# QCopterFC_MCU_Sch.net
KiCad netlist of a schematic drawn in Altium Designer
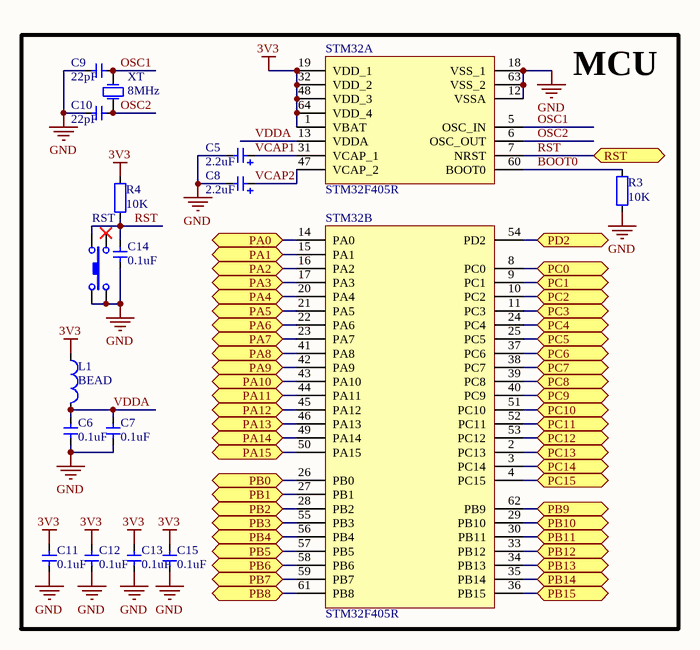
[diagram p0: QCopterFC_MCU_Sch.SchDoc]

(export (version "E")
  (design (tool "Eeschema 10.0.6"))
  (components
    (comp (ref "C5")
      (value "2.2uF")
      (footprint "PCB_Passive:CAP_TAN_P0805")
      (description "Capacitor")
      (fields (field (name "Comment") "Cap_Tan_0805"))
      (libsource (lib "SCH_Passive") (part "Cap_Tan_0805"))
    )
    (comp (ref "C6")
      (value "0.1uF")
      (footprint "PCB_Passive:CAP_0603")
      (description "Capacitor")
      (fields (field (name "Comment") "Cap_0603"))
      (libsource (lib "SCH_Passive") (part "Cap_0603"))
    )
    (comp (ref "C7")
      (value "0.1uF")
      (footprint "PCB_Passive:CAP_0603")
      (description "Capacitor")
      (fields (field (name "Comment") "Cap_0603"))
      (libsource (lib "SCH_Passive") (part "Cap_0603"))
    )
    (comp (ref "C8")
      (value "2.2uF")
      (footprint "PCB_Passive:CAP_TAN_P0805")
      (description "Capacitor")
      (fields (field (name "Comment") "Cap_Tan_0805"))
      (libsource (lib "SCH_Passive") (part "Cap_Tan_0805"))
    )
    (comp (ref "C9")
      (value "22pF")
      (footprint "PCB_Passive:CAP_0603")
      (description "Capacitor")
      (fields (field (name "Comment") "Cap_0603"))
      (libsource (lib "SCH_Passive") (part "Cap_0603"))
    )
    (comp (ref "C10")
      (value "22pF")
      (footprint "PCB_Passive:CAP_0603")
      (description "Capacitor")
      (fields (field (name "Comment") "Cap_0603"))
      (libsource (lib "SCH_Passive") (part "Cap_0603"))
    )
    (comp (ref "C11")
      (value "0.1uF")
      (footprint "PCB_Passive:CAP_0603")
      (description "Capacitor")
      (fields (field (name "Comment") "Cap_0603"))
      (libsource (lib "SCH_Passive") (part "Cap_0603"))
    )
    (comp (ref "C12")
      (value "0.1uF")
      (footprint "PCB_Passive:CAP_0603")
      (description "Capacitor")
      (fields (field (name "Comment") "Cap_0603"))
      (libsource (lib "SCH_Passive") (part "Cap_0603"))
    )
    (comp (ref "C13")
      (value "0.1uF")
      (footprint "PCB_Passive:CAP_0603")
      (description "Capacitor")
      (fields (field (name "Comment") "Cap_0603"))
      (libsource (lib "SCH_Passive") (part "Cap_0603"))
    )
    (comp (ref "C14")
      (value "0.1uF")
      (footprint "PCB_Passive:CAP_0603")
      (description "Capacitor")
      (fields (field (name "Comment") "Cap_0603"))
      (libsource (lib "SCH_Passive") (part "Cap_0603"))
    )
    (comp (ref "C15")
      (value "0.1uF")
      (footprint "PCB_Passive:CAP_0603")
      (description "Capacitor")
      (fields (field (name "Comment") "Cap_0603"))
      (libsource (lib "SCH_Passive") (part "Cap_0603"))
    )
    (comp (ref "L1")
      (value "BEAD")
      (footprint "PCB_Passive:IND_0603")
      (description "Inductor")
      (fields (field (name "Comment") "Ind_0603"))
      (libsource (lib "SCH_Passive") (part "Ind_0603"))
    )
    (comp (ref "R3")
      (value "10K")
      (footprint "PCB_Passive:RES_0603")
      (description "Resistor")
      (fields (field (name "Comment") "Res_0603"))
      (libsource (lib "SCH_Passive") (part "Res_0603"))
    )
    (comp (ref "R4")
      (value "10K")
      (footprint "PCB_Passive:RES_0603")
      (description "Resistor")
      (fields (field (name "Comment") "Res_0603"))
      (libsource (lib "SCH_Passive") (part "Res_0603"))
    )
    (comp (ref "RST")
      (value "BT_TACT_3.5*5_90")
      (footprint "PCB_Switch:BT_TACT_3.5*3.55_90")
      (description "Switch")
      (libsource (lib "SCH_Switch") (part "BT_TACT_3.5*5_90"))
    )
    (comp (ref "STM32")
      (value "STM32F405R")
      (footprint "PCB_IC:STM32_QFP64")
      (description "MCU")
      (libsource (lib "SCH_IC") (part "STM32F405R"))
    )
    (comp (ref "XT")
      (value "8MHz")
      (footprint "PCB_Oscillator:XTAL_5032")
      (description "Crystal Oscillator")
      (fields (field (name "Comment") "XTAL_5032_2P"))
      (libsource (lib "SCH_Oscillator") (part "XTAL_5032_2P"))
    )
  )
  (nets
    (net (code "1") (name "/BOOT0") (class "Default")
      (node (ref "R3") (pin "2") (pinfunction "2_2") (pintype "passive"))
      (node (ref "STM32") (pin "60") (pinfunction "BOOT0_60") (pintype "passive"))
    )
    (net (code "2") (name "/OSC1") (class "Default")
      (node (ref "C9") (pin "2") (pinfunction "2_2") (pintype "passive"))
      (node (ref "STM32") (pin "5") (pinfunction "OSC_IN_5") (pintype "passive"))
      (node (ref "XT") (pin "2") (pinfunction "OSC2_2") (pintype "passive"))
    )
    (net (code "3") (name "/OSC2") (class "Default")
      (node (ref "C10") (pin "2") (pinfunction "2_2") (pintype "passive"))
      (node (ref "STM32") (pin "6") (pinfunction "OSC_OUT_6") (pintype "passive"))
      (node (ref "XT") (pin "1") (pinfunction "OSC1_1") (pintype "passive"))
    )
    (net (code "4") (name "/PA0") (class "Default")
      (node (ref "STM32") (pin "14") (pinfunction "PA0_14") (pintype "passive"))
    )
    (net (code "5") (name "/PA1") (class "Default")
      (node (ref "STM32") (pin "15") (pinfunction "PA1_15") (pintype "passive"))
    )
    (net (code "6") (name "/PA2") (class "Default")
      (node (ref "STM32") (pin "16") (pinfunction "PA2_16") (pintype "passive"))
    )
    (net (code "7") (name "/PA3") (class "Default")
      (node (ref "STM32") (pin "17") (pinfunction "PA3_17") (pintype "passive"))
    )
    (net (code "8") (name "/PA4") (class "Default")
      (node (ref "STM32") (pin "20") (pinfunction "PA4_20") (pintype "passive"))
    )
    (net (code "9") (name "/PA5") (class "Default")
      (node (ref "STM32") (pin "21") (pinfunction "PA5_21") (pintype "passive"))
    )
    (net (code "10") (name "/PA6") (class "Default")
      (node (ref "STM32") (pin "22") (pinfunction "PA6_22") (pintype "passive"))
    )
    (net (code "11") (name "/PA7") (class "Default")
      (node (ref "STM32") (pin "23") (pinfunction "PA7_23") (pintype "passive"))
    )
    (net (code "12") (name "/PA8") (class "Default")
      (node (ref "STM32") (pin "41") (pinfunction "PA8_41") (pintype "passive"))
    )
    (net (code "13") (name "/PA9") (class "Default")
      (node (ref "STM32") (pin "42") (pinfunction "PA9_42") (pintype "passive"))
    )
    (net (code "14") (name "/PA10") (class "Default")
      (node (ref "STM32") (pin "43") (pinfunction "PA10_43") (pintype "passive"))
    )
    (net (code "15") (name "/PA11") (class "Default")
      (node (ref "STM32") (pin "44") (pinfunction "PA11_44") (pintype "passive"))
    )
    (net (code "16") (name "/PA12") (class "Default")
      (node (ref "STM32") (pin "45") (pinfunction "PA12_45") (pintype "passive"))
    )
    (net (code "17") (name "/PA13") (class "Default")
      (node (ref "STM32") (pin "46") (pinfunction "PA13_46") (pintype "passive"))
    )
    (net (code "18") (name "/PA14") (class "Default")
      (node (ref "STM32") (pin "49") (pinfunction "PA14_49") (pintype "passive"))
    )
    (net (code "19") (name "/PA15") (class "Default")
      (node (ref "STM32") (pin "50") (pinfunction "PA15_50") (pintype "passive"))
    )
    (net (code "20") (name "/PB0") (class "Default")
      (node (ref "STM32") (pin "26") (pinfunction "PB0_26") (pintype "passive"))
    )
    (net (code "21") (name "/PB1") (class "Default")
      (node (ref "STM32") (pin "27") (pinfunction "PB1_27") (pintype "passive"))
    )
    (net (code "22") (name "/PB2") (class "Default")
      (node (ref "STM32") (pin "28") (pinfunction "PB2_28") (pintype "passive"))
    )
    (net (code "23") (name "/PB3") (class "Default")
      (node (ref "STM32") (pin "55") (pinfunction "PB3_55") (pintype "passive"))
    )
    (net (code "24") (name "/PB4") (class "Default")
      (node (ref "STM32") (pin "56") (pinfunction "PB4_56") (pintype "passive"))
    )
    (net (code "25") (name "/PB5") (class "Default")
      (node (ref "STM32") (pin "57") (pinfunction "PB5_57") (pintype "passive"))
    )
    (net (code "26") (name "/PB6") (class "Default")
      (node (ref "STM32") (pin "58") (pinfunction "PB6_58") (pintype "passive"))
    )
    (net (code "27") (name "/PB7") (class "Default")
      (node (ref "STM32") (pin "59") (pinfunction "PB7_59") (pintype "passive"))
    )
    (net (code "28") (name "/PB8") (class "Default")
      (node (ref "STM32") (pin "61") (pinfunction "PB8_61") (pintype "passive"))
    )
    (net (code "29") (name "/PB9") (class "Default")
      (node (ref "STM32") (pin "62") (pinfunction "PB9_62") (pintype "passive"))
    )
    (net (code "30") (name "/PB10") (class "Default")
      (node (ref "STM32") (pin "29") (pinfunction "PB10_29") (pintype "passive"))
    )
    (net (code "31") (name "/PB11") (class "Default")
      (node (ref "STM32") (pin "30") (pinfunction "PB11_30") (pintype "passive"))
    )
    (net (code "32") (name "/PB12") (class "Default")
      (node (ref "STM32") (pin "33") (pinfunction "PB12_33") (pintype "passive"))
    )
    (net (code "33") (name "/PB13") (class "Default")
      (node (ref "STM32") (pin "34") (pinfunction "PB13_34") (pintype "passive"))
    )
    (net (code "34") (name "/PB14") (class "Default")
      (node (ref "STM32") (pin "35") (pinfunction "PB14_35") (pintype "passive"))
    )
    (net (code "35") (name "/PB15") (class "Default")
      (node (ref "STM32") (pin "36") (pinfunction "PB15_36") (pintype "passive"))
    )
    (net (code "36") (name "/PC0") (class "Default")
      (node (ref "STM32") (pin "8") (pinfunction "PC0_8") (pintype "passive"))
    )
    (net (code "37") (name "/PC1") (class "Default")
      (node (ref "STM32") (pin "9") (pinfunction "PC1_9") (pintype "passive"))
    )
    (net (code "38") (name "/PC2") (class "Default")
      (node (ref "STM32") (pin "10") (pinfunction "PC2_10") (pintype "passive"))
    )
    (net (code "39") (name "/PC3") (class "Default")
      (node (ref "STM32") (pin "11") (pinfunction "PC3_11") (pintype "passive"))
    )
    (net (code "40") (name "/PC4") (class "Default")
      (node (ref "STM32") (pin "24") (pinfunction "PC4_24") (pintype "passive"))
    )
    (net (code "41") (name "/PC5") (class "Default")
      (node (ref "STM32") (pin "25") (pinfunction "PC5_25") (pintype "passive"))
    )
    (net (code "42") (name "/PC6") (class "Default")
      (node (ref "STM32") (pin "37") (pinfunction "PC6_37") (pintype "passive"))
    )
    (net (code "43") (name "/PC7") (class "Default")
      (node (ref "STM32") (pin "38") (pinfunction "PC7_38") (pintype "passive"))
    )
    (net (code "44") (name "/PC8") (class "Default")
      (node (ref "STM32") (pin "39") (pinfunction "PC8_39") (pintype "passive"))
    )
    (net (code "45") (name "/PC9") (class "Default")
      (node (ref "STM32") (pin "40") (pinfunction "PC9_40") (pintype "passive"))
    )
    (net (code "46") (name "/PC10") (class "Default")
      (node (ref "STM32") (pin "51") (pinfunction "PC10_51") (pintype "passive"))
    )
    (net (code "47") (name "/PC11") (class "Default")
      (node (ref "STM32") (pin "52") (pinfunction "PC11_52") (pintype "passive"))
    )
    (net (code "48") (name "/PC12") (class "Default")
      (node (ref "STM32") (pin "53") (pinfunction "PC12_53") (pintype "passive"))
    )
    (net (code "49") (name "/PC13") (class "Default")
      (node (ref "STM32") (pin "2") (pinfunction "PC13_2") (pintype "passive"))
    )
    (net (code "50") (name "/PC14") (class "Default")
      (node (ref "STM32") (pin "3") (pinfunction "PC14_3") (pintype "passive"))
    )
    (net (code "51") (name "/PC15") (class "Default")
      (node (ref "STM32") (pin "4") (pinfunction "PC15_4") (pintype "passive"))
    )
    (net (code "52") (name "/PD2") (class "Default")
      (node (ref "STM32") (pin "54") (pinfunction "PD2_54") (pintype "passive"))
    )
    (net (code "53") (name "/RST") (class "Default")
      (node (ref "C14") (pin "1") (pinfunction "1_1") (pintype "passive"))
      (node (ref "R4") (pin "1") (pinfunction "1_1") (pintype "passive"))
      (node (ref "RST") (pin "2") (pinfunction "2_2") (pintype "passive"))
      (node (ref "STM32") (pin "7") (pinfunction "NRST_7") (pintype "passive"))
    )
    (net (code "54") (name "/VCAP1") (class "Default")
      (node (ref "C5") (pin "1") (pinfunction "1_1") (pintype "passive"))
      (node (ref "STM32") (pin "31") (pinfunction "VCAP_1_31") (pintype "passive"))
    )
    (net (code "55") (name "/VCAP2") (class "Default")
      (node (ref "C8") (pin "1") (pinfunction "1_1") (pintype "passive"))
      (node (ref "STM32") (pin "47") (pinfunction "VCAP_2_47") (pintype "passive"))
    )
    (net (code "56") (name "/VDDA") (class "Default")
      (node (ref "C6") (pin "2") (pinfunction "2_2") (pintype "passive"))
      (node (ref "C7") (pin "2") (pinfunction "2_2") (pintype "passive"))
      (node (ref "L1") (pin "2") (pinfunction "2_2") (pintype "passive"))
      (node (ref "STM32") (pin "13") (pinfunction "VDDA_13") (pintype "passive"))
    )
    (net (code "57") (name "3V3") (class "Default")
      (node (ref "C11") (pin "1") (pinfunction "1_1") (pintype "passive"))
      (node (ref "C12") (pin "1") (pinfunction "1_1") (pintype "passive"))
      (node (ref "C13") (pin "1") (pinfunction "1_1") (pintype "passive"))
      (node (ref "C15") (pin "1") (pinfunction "1_1") (pintype "passive"))
      (node (ref "L1") (pin "1") (pinfunction "1_1") (pintype "passive"))
      (node (ref "R4") (pin "2") (pinfunction "2_2") (pintype "passive"))
      (node (ref "STM32") (pin "1") (pinfunction "VBAT_1") (pintype "passive"))
      (node (ref "STM32") (pin "19") (pinfunction "VDD_1_19") (pintype "passive"))
      (node (ref "STM32") (pin "32") (pinfunction "VDD_2_32") (pintype "passive"))
      (node (ref "STM32") (pin "48") (pinfunction "VDD_3_48") (pintype "passive"))
      (node (ref "STM32") (pin "64") (pinfunction "VDD_4_64") (pintype "passive"))
    )
    (net (code "58") (name "GND") (class "Default")
      (node (ref "C10") (pin "1") (pinfunction "1_1") (pintype "passive"))
      (node (ref "C11") (pin "2") (pinfunction "2_2") (pintype "passive"))
      (node (ref "C12") (pin "2") (pinfunction "2_2") (pintype "passive"))
      (node (ref "C13") (pin "2") (pinfunction "2_2") (pintype "passive"))
      (node (ref "C14") (pin "2") (pinfunction "2_2") (pintype "passive"))
      (node (ref "C15") (pin "2") (pinfunction "2_2") (pintype "passive"))
      (node (ref "C5") (pin "2") (pinfunction "2_2") (pintype "passive"))
      (node (ref "C6") (pin "1") (pinfunction "1_1") (pintype "passive"))
      (node (ref "C7") (pin "1") (pinfunction "1_1") (pintype "passive"))
      (node (ref "C8") (pin "2") (pinfunction "2_2") (pintype "passive"))
      (node (ref "C9") (pin "1") (pinfunction "1_1") (pintype "passive"))
      (node (ref "R3") (pin "1") (pinfunction "1_1") (pintype "passive"))
      (node (ref "RST") (pin "1") (pinfunction "1_1") (pintype "passive"))
      (node (ref "RST") (pin "3") (pinfunction "3_3") (pintype "passive"))
      (node (ref "STM32") (pin "12") (pinfunction "VSSA_12") (pintype "passive"))
      (node (ref "STM32") (pin "18") (pinfunction "VSS_1_18") (pintype "passive"))
      (node (ref "STM32") (pin "63") (pinfunction "VSS_2_63") (pintype "passive"))
    )
    (net (code "59") (name "unconnected-(RST-Pad4)") (class "Default")
      (node (ref "RST") (pin "4") (pinfunction "4_4") (pintype "passive+no_connect"))
    )
  )
)
